# 3-HT16K33.net
KiCad netlist of a schematic drawn in Altium Designer
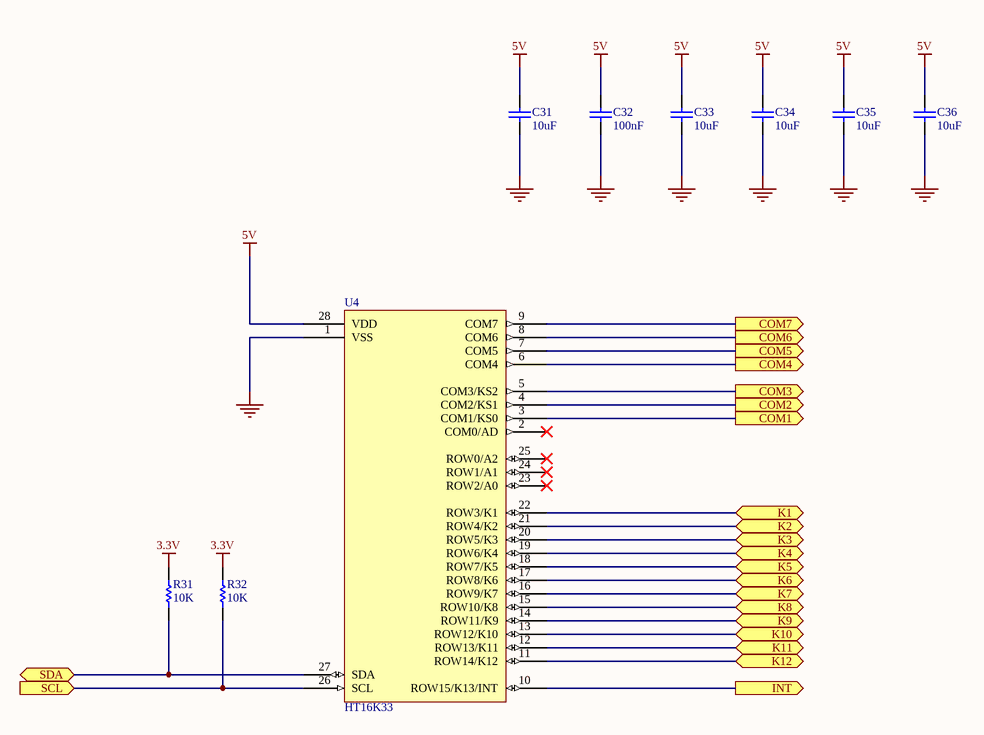
[diagram p0: 3-HT16K33.SchDoc]

(export (version "E")
  (design (tool "Eeschema 10.0.6"))
  (components
    (comp (ref "C31")
      (value "10uF")
      (footprint "capa 1206")
      (description "Capacitor")
      (libsource (lib "Miscellaneous Devices") (part "Cap"))
    )
    (comp (ref "C32")
      (value "100nF")
      (footprint "capa 1206")
      (description "Capacitor")
      (libsource (lib "Miscellaneous Devices") (part "Cap"))
    )
    (comp (ref "C33")
      (value "10uF")
      (footprint "capa 1206")
      (description "Capacitor")
      (libsource (lib "Miscellaneous Devices") (part "Cap"))
    )
    (comp (ref "C34")
      (value "10uF")
      (footprint "capa 1206")
      (description "Capacitor")
      (libsource (lib "Miscellaneous Devices") (part "Cap"))
    )
    (comp (ref "C35")
      (value "10uF")
      (footprint "capa 1206")
      (description "Capacitor")
      (libsource (lib "Miscellaneous Devices") (part "Cap"))
    )
    (comp (ref "C36")
      (value "10uF")
      (footprint "capa 1206")
      (description "Capacitor")
      (libsource (lib "Miscellaneous Devices") (part "Cap"))
    )
    (comp (ref "R31")
      (value "10K")
      (footprint "RES 1206")
      (description "Resistor")
      (libsource (lib "Miscellaneous Devices") (part "Res1"))
    )
    (comp (ref "R32")
      (value "10K")
      (footprint "RES 1206")
      (description "Resistor")
      (libsource (lib "Miscellaneous Devices") (part "Res1"))
    )
    (comp (ref "U4")
      (value "HT16K33")
      (footprint "HT16K33 SOP")
      (libsource (lib "0x2a002a") (part "HT16K33"))
    )
  )
  (nets
    (net (code "1") (name "/COM1") (class "Default")
      (node (ref "U4") (pin "3") (pinfunction "COM1/KS0_3") (pintype "output"))
    )
    (net (code "2") (name "/COM2") (class "Default")
      (node (ref "U4") (pin "4") (pinfunction "COM2/KS1_4") (pintype "output"))
    )
    (net (code "3") (name "/COM3") (class "Default")
      (node (ref "U4") (pin "5") (pinfunction "COM3/KS2_5") (pintype "output"))
    )
    (net (code "4") (name "/COM4") (class "Default")
      (node (ref "U4") (pin "6") (pinfunction "COM4_6") (pintype "output"))
    )
    (net (code "5") (name "/COM5") (class "Default")
      (node (ref "U4") (pin "7") (pinfunction "COM5_7") (pintype "output"))
    )
    (net (code "6") (name "/COM6") (class "Default")
      (node (ref "U4") (pin "8") (pinfunction "COM6_8") (pintype "output"))
    )
    (net (code "7") (name "/COM7") (class "Default")
      (node (ref "U4") (pin "9") (pinfunction "COM7_9") (pintype "output"))
    )
    (net (code "8") (name "/INT") (class "Default")
      (node (ref "U4") (pin "10") (pinfunction "ROW15/K13/INT_10") (pintype "bidirectional"))
    )
    (net (code "9") (name "/K1") (class "Default")
      (node (ref "U4") (pin "22") (pinfunction "ROW3/K1_22") (pintype "bidirectional"))
    )
    (net (code "10") (name "/K2") (class "Default")
      (node (ref "U4") (pin "21") (pinfunction "ROW4/K2_21") (pintype "bidirectional"))
    )
    (net (code "11") (name "/K3") (class "Default")
      (node (ref "U4") (pin "20") (pinfunction "ROW5/K3_20") (pintype "bidirectional"))
    )
    (net (code "12") (name "/K4") (class "Default")
      (node (ref "U4") (pin "19") (pinfunction "ROW6/K4_19") (pintype "bidirectional"))
    )
    (net (code "13") (name "/K5") (class "Default")
      (node (ref "U4") (pin "18") (pinfunction "ROW7/K5_18") (pintype "bidirectional"))
    )
    (net (code "14") (name "/K6") (class "Default")
      (node (ref "U4") (pin "17") (pinfunction "ROW8/K6_17") (pintype "bidirectional"))
    )
    (net (code "15") (name "/K7") (class "Default")
      (node (ref "U4") (pin "16") (pinfunction "ROW9/K7_16") (pintype "bidirectional"))
    )
    (net (code "16") (name "/K8") (class "Default")
      (node (ref "U4") (pin "15") (pinfunction "ROW10/K8_15") (pintype "bidirectional"))
    )
    (net (code "17") (name "/K9") (class "Default")
      (node (ref "U4") (pin "14") (pinfunction "ROW11/K9_14") (pintype "bidirectional"))
    )
    (net (code "18") (name "/K10") (class "Default")
      (node (ref "U4") (pin "13") (pinfunction "ROW12/K10_13") (pintype "bidirectional"))
    )
    (net (code "19") (name "/K11") (class "Default")
      (node (ref "U4") (pin "12") (pinfunction "ROW13/K11_12") (pintype "bidirectional"))
    )
    (net (code "20") (name "/K12") (class "Default")
      (node (ref "U4") (pin "11") (pinfunction "ROW14/K12_11") (pintype "bidirectional"))
    )
    (net (code "21") (name "/SCL") (class "Default")
      (node (ref "R32") (pin "1") (pinfunction "1_1") (pintype "passive"))
      (node (ref "U4") (pin "26") (pinfunction "SCL_26") (pintype "input"))
    )
    (net (code "22") (name "/SDA") (class "Default")
      (node (ref "R31") (pin "2") (pinfunction "2_2") (pintype "passive"))
      (node (ref "U4") (pin "27") (pinfunction "SDA_27") (pintype "bidirectional"))
    )
    (net (code "23") (name "3.3V") (class "Default")
      (node (ref "R31") (pin "1") (pinfunction "1_1") (pintype "passive"))
      (node (ref "R32") (pin "2") (pinfunction "2_2") (pintype "passive"))
    )
    (net (code "24") (name "5V") (class "Default")
      (node (ref "C31") (pin "2") (pinfunction "2_2") (pintype "passive"))
      (node (ref "C32") (pin "2") (pinfunction "2_2") (pintype "passive"))
      (node (ref "C33") (pin "2") (pinfunction "2_2") (pintype "passive"))
      (node (ref "C34") (pin "2") (pinfunction "2_2") (pintype "passive"))
      (node (ref "C35") (pin "2") (pinfunction "2_2") (pintype "passive"))
      (node (ref "C36") (pin "2") (pinfunction "2_2") (pintype "passive"))
      (node (ref "U4") (pin "28") (pinfunction "VDD_28") (pintype "power_in"))
    )
    (net (code "25") (name "GND") (class "Default")
      (node (ref "C31") (pin "1") (pinfunction "1_1") (pintype "passive"))
      (node (ref "C32") (pin "1") (pinfunction "1_1") (pintype "passive"))
      (node (ref "C33") (pin "1") (pinfunction "1_1") (pintype "passive"))
      (node (ref "C34") (pin "1") (pinfunction "1_1") (pintype "passive"))
      (node (ref "C35") (pin "1") (pinfunction "1_1") (pintype "passive"))
      (node (ref "C36") (pin "1") (pinfunction "1_1") (pintype "passive"))
      (node (ref "U4") (pin "1") (pinfunction "VSS_1") (pintype "power_in"))
    )
    (net (code "26") (name "unconnected-(U4-COM0{slash}AD-Pad2)") (class "Default")
      (node (ref "U4") (pin "2") (pinfunction "COM0/AD_2") (pintype "output+no_connect"))
    )
    (net (code "27") (name "unconnected-(U4-ROW0{slash}A2-Pad25)") (class "Default")
      (node (ref "U4") (pin "25") (pinfunction "ROW0/A2_25") (pintype "bidirectional+no_connect"))
    )
    (net (code "28") (name "unconnected-(U4-ROW1{slash}A1-Pad24)") (class "Default")
      (node (ref "U4") (pin "24") (pinfunction "ROW1/A1_24") (pintype "bidirectional+no_connect"))
    )
    (net (code "29") (name "unconnected-(U4-ROW2{slash}A0-Pad23)") (class "Default")
      (node (ref "U4") (pin "23") (pinfunction "ROW2/A0_23") (pintype "bidirectional+no_connect"))
    )
  )
)
